# mainboard.net
KiCad netlist of a schematic drawn in Altium Designer
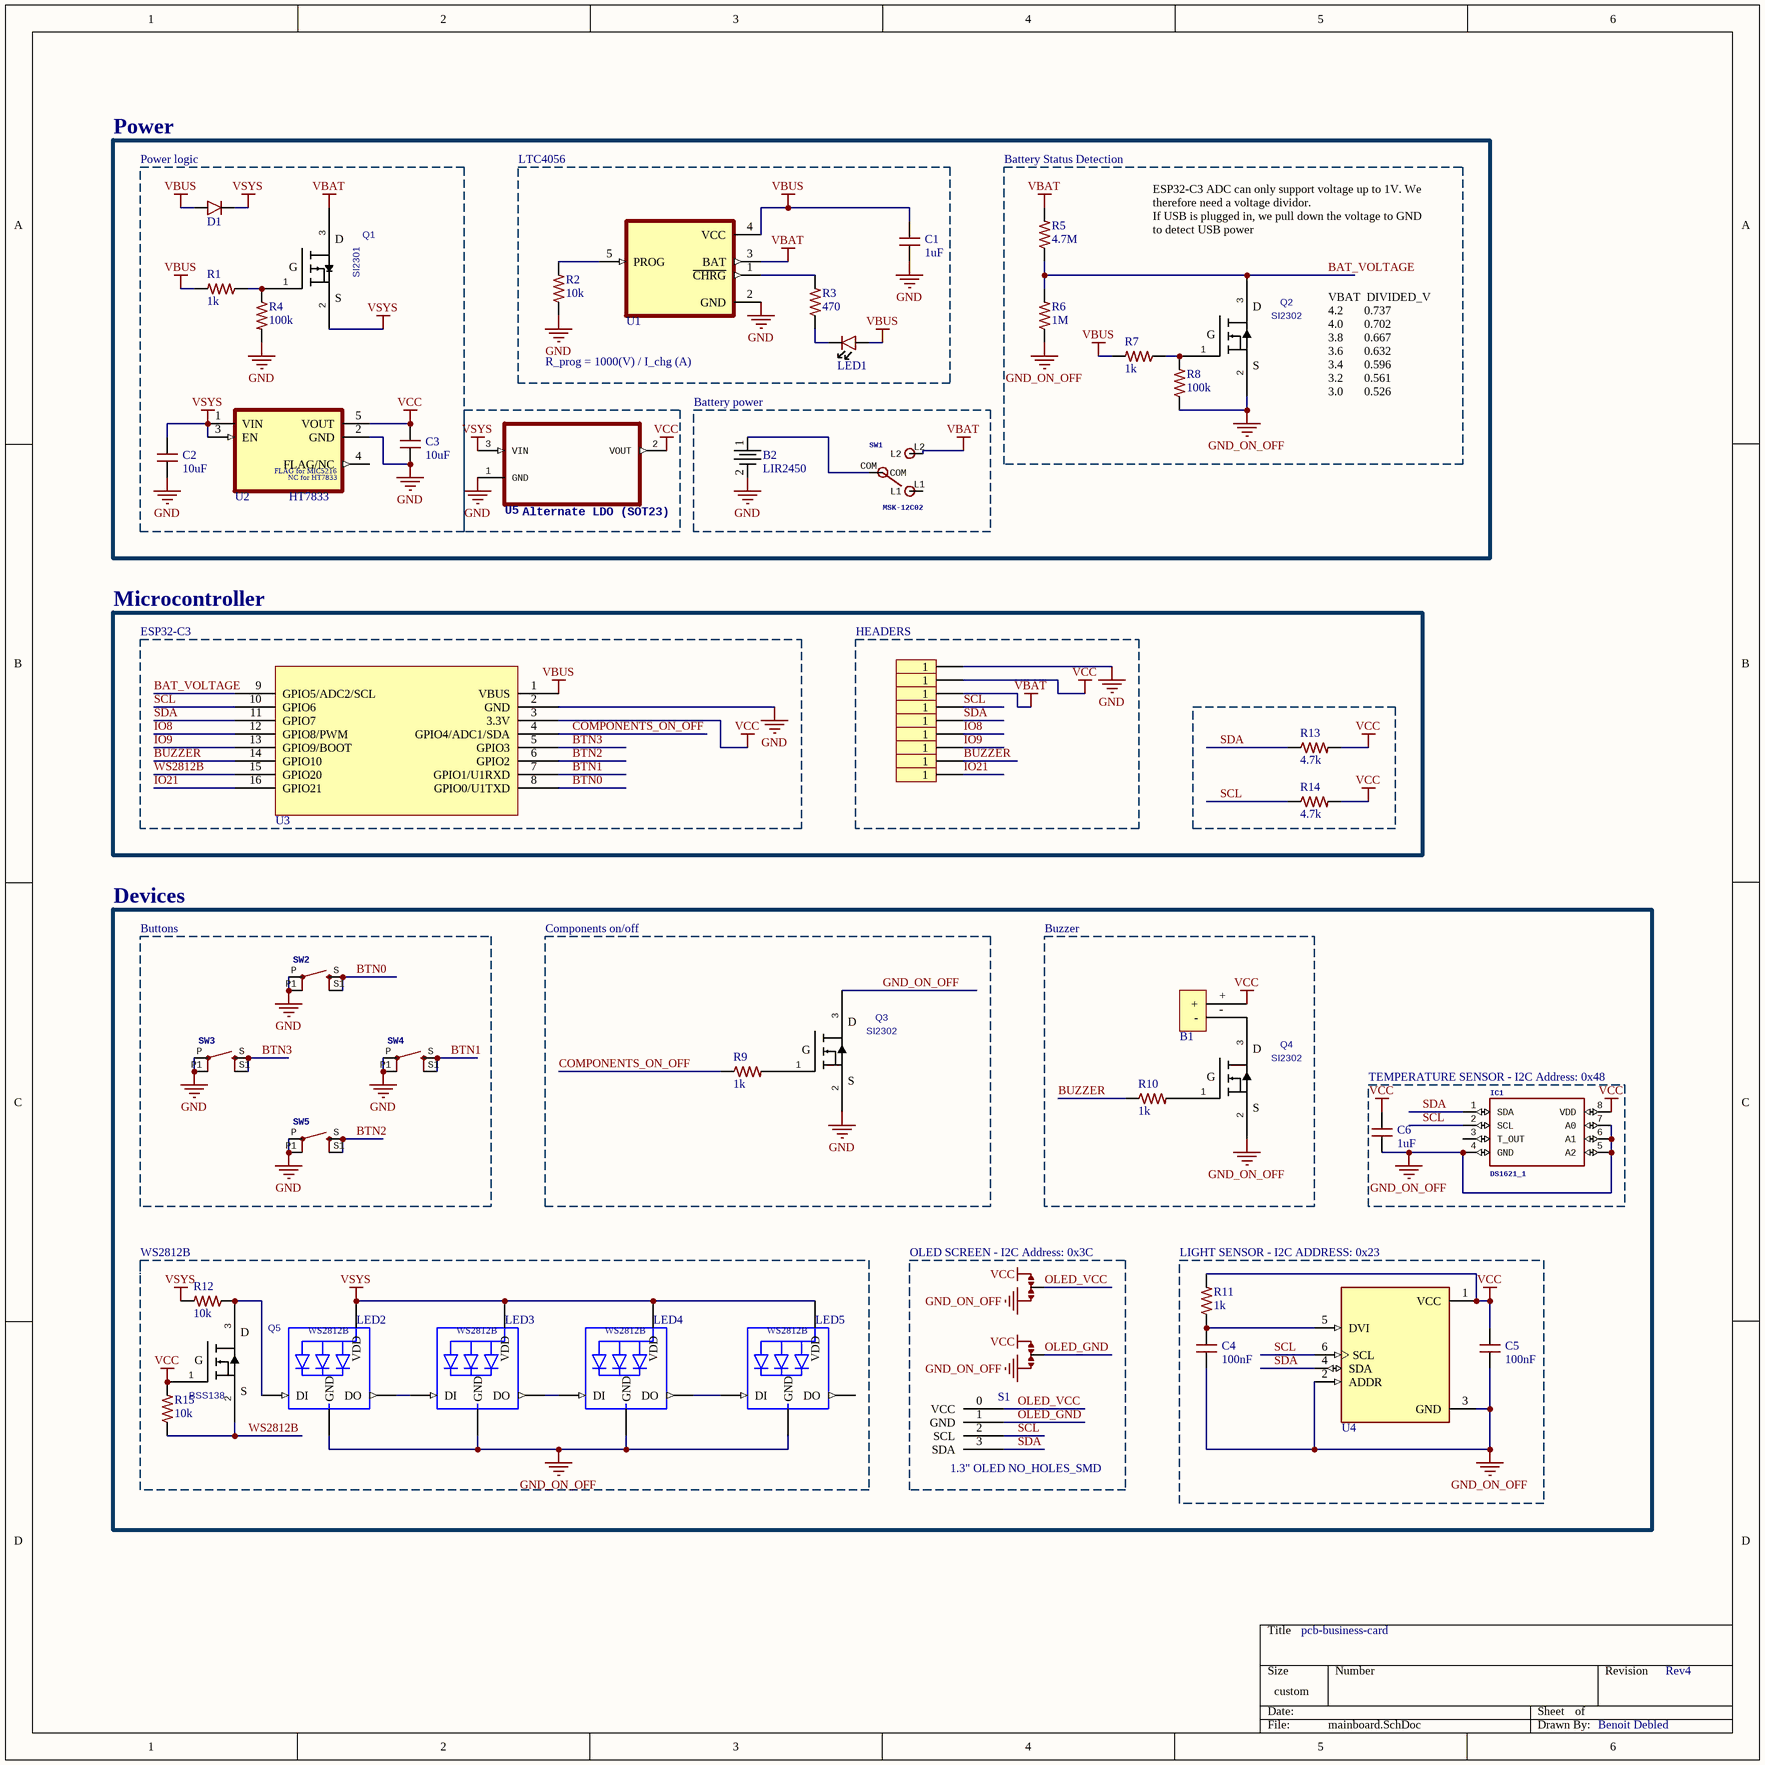
[diagram p0: mainboard.SchDoc]

(export (version "E")
  (design (tool "Eeschema 10.0.6"))
  (components
    (comp (ref "*")
      (value "PAD 1")
      (footprint "PAD_50mil_x_80mil")
      (libsource (lib "bd-header") (part "PAD 1"))
    )
    (comp (ref "*1")
      (value "PAD 1")
      (footprint "PAD_50mil_x_80mil")
      (libsource (lib "bd-header") (part "PAD 1"))
    )
    (comp (ref "*2")
      (value "PAD 1")
      (footprint "PAD_50mil_x_80mil")
      (libsource (lib "bd-header") (part "PAD 1"))
    )
    (comp (ref "*3")
      (value "PAD 1")
      (footprint "PAD_50mil_x_80mil")
      (libsource (lib "bd-header") (part "PAD 1"))
    )
    (comp (ref "*4")
      (value "PAD 1")
      (footprint "PAD_50mil_x_80mil")
      (libsource (lib "bd-header") (part "PAD 1"))
    )
    (comp (ref "*5")
      (value "PAD 1")
      (footprint "PAD_50mil_x_80mil")
      (libsource (lib "bd-header") (part "PAD 1"))
    )
    (comp (ref "*6")
      (value "PAD 1")
      (footprint "PAD_50mil_x_80mil")
      (libsource (lib "bd-header") (part "PAD 1"))
    )
    (comp (ref "*7")
      (value "PAD 1")
      (footprint "PAD_50mil_x_80mil")
      (libsource (lib "bd-header") (part "PAD 1"))
    )
    (comp (ref "*8")
      (value "PAD 1")
      (footprint "PAD_50mil_x_80mil")
      (libsource (lib "bd-header") (part "PAD 1"))
    )
    (comp (ref "B1")
      (value "Buzzer5x5x2")
      (footprint "BUZZER_5x5x2")
      (libsource (lib "bd-component") (part "Buzzer5x5x2"))
    )
    (comp (ref "B2")
      (value "LIR2450")
      (footprint "LIR2450")
      (libsource (lib "bd-component") (part "LIR2450"))
    )
    (comp (ref "C1") (value "1uF") (footprint "C0805K") (libsource (lib "bd-generics") (part "C-USC0805K")))
    (comp (ref "C2") (value "10uF") (footprint "C0805K") (libsource (lib "bd-generics") (part "C-USC0805K")))
    (comp (ref "C3") (value "10uF") (footprint "C0805K") (libsource (lib "bd-generics") (part "C-USC0805K")))
    (comp (ref "C4") (value "100nF") (footprint "C0805K") (libsource (lib "bd-generics") (part "C-USC0805K")))
    (comp (ref "C5") (value "100nF") (footprint "C0805K") (libsource (lib "bd-generics") (part "C-USC0805K")))
    (comp (ref "C6") (value "1uF") (footprint "C0805K") (libsource (lib "bd-generics") (part "C-USC0805K")))
    (comp (ref "D1")
      (value "Diode_M7")
      (footprint "DO-214")
      (libsource (lib "bd-generics") (part "Diode_M7"))
    )
    (comp (ref "IC1")
      (value "DS1621_1")
      (footprint "SOP-8")
      (libsource (lib "bd-component") (part "DS1621_1"))
    )
    (comp (ref "JMP1") (value "0R-JUMPA") (footprint "A0R-JMP") (libsource (lib "bd-misc") (part "0R-JUMPA")))
    (comp (ref "JMP2") (value "0R-JUMPA") (footprint "A0R-JMP") (libsource (lib "bd-misc") (part "0R-JUMPA")))
    (comp (ref "LED1") (value "LED") (footprint "LED0805K") (libsource (lib "bd-generics") (part "LED")))
    (comp (ref "LED2")
      (value "WS2812B")
      (footprint "WS2812B")
      (description "Raspberry Pi HAT _40 pin_ Wheeled Robotics Kit")
      (fields (field (name "MF") "SparkFun Electronics"))
      (libsource (lib "bd-component") (part "WS2812B"))
    )
    (comp (ref "LED3")
      (value "WS2812B")
      (footprint "WS2812B")
      (description "Raspberry Pi HAT _40 pin_ Wheeled Robotics Kit")
      (fields (field (name "MF") "SparkFun Electronics"))
      (libsource (lib "bd-component") (part "WS2812B"))
    )
    (comp (ref "LED4")
      (value "WS2812B")
      (footprint "WS2812B")
      (description "Raspberry Pi HAT _40 pin_ Wheeled Robotics Kit")
      (fields (field (name "MF") "SparkFun Electronics"))
      (libsource (lib "bd-component") (part "WS2812B"))
    )
    (comp (ref "LED5")
      (value "WS2812B")
      (footprint "WS2812B")
      (description "Raspberry Pi HAT _40 pin_ Wheeled Robotics Kit")
      (fields (field (name "MF") "SparkFun Electronics"))
      (libsource (lib "bd-component") (part "WS2812B"))
    )
    (comp (ref "Q1")
      (value "SI2301")
      (footprint "SOT-23")
      (fields
        (field (name "MANUFACTURER_PART_NUMBER") "IRLZ44NPBF")
        (field (name "COPYRIGHT") "Copyright (C) 2018 Accelerated Designs. All rights reserved")
      )
      (libsource (lib "bd-transistor") (part "SI2301"))
    )
    (comp (ref "Q2")
      (value "SI2302")
      (footprint "SOT-23")
      (fields
        (field (name "MANUFACTURER_PART_NUMBER") "IRLZ44NPBF")
        (field (name "COPYRIGHT") "Copyright (C) 2018 Accelerated Designs. All rights reserved")
      )
      (libsource (lib "bd-transistor") (part "SI2302"))
    )
    (comp (ref "Q3")
      (value "SI2302")
      (footprint "SOT-23")
      (fields
        (field (name "MANUFACTURER_PART_NUMBER") "IRLZ44NPBF")
        (field (name "COPYRIGHT") "Copyright (C) 2018 Accelerated Designs. All rights reserved")
      )
      (libsource (lib "bd-transistor") (part "SI2302"))
    )
    (comp (ref "Q4")
      (value "SI2302")
      (footprint "SOT-23")
      (fields
        (field (name "MANUFACTURER_PART_NUMBER") "IRLZ44NPBF")
        (field (name "COPYRIGHT") "Copyright (C) 2018 Accelerated Designs. All rights reserved")
      )
      (libsource (lib "bd-transistor") (part "SI2302"))
    )
    (comp (ref "Q5")
      (value "BSS138")
      (footprint "SOT-23")
      (fields
        (field (name "MANUFACTURER_PART_NUMBER") "IRLZ44NPBF")
        (field (name "COPYRIGHT") "Copyright (C) 2018 Accelerated Designs. All rights reserved")
      )
      (libsource (lib "bd-transistor") (part "SI2302"))
    )
    (comp (ref "R1") (value "1k") (footprint "R0805W") (libsource (lib "bd-generics") (part "R-US_R0805W")))
    (comp (ref "R2") (value "10k") (footprint "R0805W") (libsource (lib "bd-generics") (part "R-US_R0805W")))
    (comp (ref "R3") (value "470") (footprint "R0805W") (libsource (lib "bd-generics") (part "R-US_R0805W")))
    (comp (ref "R4") (value "100k") (footprint "R0805W") (libsource (lib "bd-generics") (part "R-US_R0805W")))
    (comp (ref "R5") (value "4.7M") (footprint "R0805W") (libsource (lib "bd-generics") (part "R-US_R0805W")))
    (comp (ref "R6") (value "1M") (footprint "R0805W") (libsource (lib "bd-generics") (part "R-US_R0805W")))
    (comp (ref "R7") (value "1k") (footprint "R0805W") (libsource (lib "bd-generics") (part "R-US_R0805W")))
    (comp (ref "R8") (value "100k") (footprint "R0805W") (libsource (lib "bd-generics") (part "R-US_R0805W")))
    (comp (ref "R9") (value "1k") (footprint "R0805W") (libsource (lib "bd-generics") (part "R-US_R0805W")))
    (comp (ref "R10") (value "1k") (footprint "R0805W") (libsource (lib "bd-generics") (part "R-US_R0805W")))
    (comp (ref "R11") (value "1k") (footprint "R0805W") (libsource (lib "bd-generics") (part "R-US_R0805W")))
    (comp (ref "R12") (value "10k") (footprint "R0805W") (libsource (lib "bd-generics") (part "R-US_R0805W")))
    (comp (ref "R13") (value "4.7k") (footprint "R0805K") (libsource (lib "bd-generics") (part "R-US_R0805")))
    (comp (ref "R14") (value "4.7k") (footprint "R0805K") (libsource (lib "bd-generics") (part "R-US_R0805")))
    (comp (ref "R15") (value "10k") (footprint "R0805W") (libsource (lib "bd-generics") (part "R-US_R0805W")))
    (comp (ref "S1")
      (value "1.3\" OLED NO_HOLES_SMD")
      (footprint "1.3_NO-holes_SMD")
      (libsource (lib "bd-display") (part "1.3{dblquote} OLED NO_HOLES_SMD"))
    )
    (comp (ref "SW1")
      (value "MSK-12C02")
      (footprint "MSK-12C02")
      (libsource (lib "bd-switch") (part "MSK-12C02"))
    )
    (comp (ref "SW2")
      (value "10-XX-6MD")
      (footprint "BT6X6")
      (libsource (lib "bd-switch") (part "10-XX-6MD"))
    )
    (comp (ref "SW3")
      (value "10-XX-6MD")
      (footprint "BT6X6")
      (libsource (lib "bd-switch") (part "10-XX-6MD"))
    )
    (comp (ref "SW4")
      (value "10-XX-6MD")
      (footprint "BT6X6")
      (libsource (lib "bd-switch") (part "10-XX-6MD"))
    )
    (comp (ref "SW5")
      (value "10-XX-6MD")
      (footprint "BT6X6")
      (libsource (lib "bd-switch") (part "10-XX-6MD"))
    )
    (comp (ref "U1")
      (value "LTC4054")
      (footprint "SOT23-5")
      (description "Battery Charger Li-Ion 10mA to 150mA 4.2V 5-Pin TSOT-23 T/R")
      (fields (field (name "MP") "LTC4054LES5-4.2#TRPBF") (field (name "MF") "Analog Devices"))
      (libsource (lib "bd-component") (part "LTC4054"))
    )
    (comp (ref "U2")
      (value "HT7833")
      (footprint "SOT23-5")
      (description "LDO Regulator")
      (fields (field (name "MP") "LTC4054LES5-4.2#TRPBF") (field (name "MF") "Analog Devices"))
      (libsource (lib "bd-component") (part "HT7833-MIC5216"))
    )
    (comp (ref "U3")
      (value "ESP32C3")
      (footprint "ESP32-C3-module")
      (libsource (lib "bd-microcontroller") (part "ESP32C3"))
    )
    (comp (ref "U4")
      (value "BH1750")
      (footprint "XDCR_BH1750FVI-TR")
      (description "Optical Sensor Ambient 560nm IÂ²C 6-SMD, Flat Lead Exposed Pad")
      (fields (field (name "MF") "Rohm") (field (name "MP") "BH1750FVI-TR"))
      (libsource (lib "bd-component") (part "BH1750"))
    )
    (comp (ref "U5")
      (value "Alternate LDO (SOT23)")
      (footprint "SOT95P237X112-3N")
      (fields (field (name "MPN") "MCP1700T-3302E/TT"))
      (libsource (lib "bd-component") (part "MCP1700T-3302E/TT"))
    )
  )
  (nets
    (net (code "1") (name "/BAT_VOLTAGE") (class "Default")
      (node (ref "Q2") (pin "3") (pinfunction "D_3") (pintype "passive"))
      (node (ref "R5") (pin "1") (pinfunction "1_1") (pintype "passive"))
      (node (ref "R6") (pin "2") (pinfunction "2_2") (pintype "passive"))
      (node (ref "U3") (pin "9") (pinfunction "GPIO5/ADC2/SCL_9") (pintype "passive"))
    )
    (net (code "2") (name "/BTN0") (class "Default")
      (node (ref "SW2") (pin "S") (pinfunction "S_S") (pintype "passive"))
      (node (ref "SW2") (pin "S1") (pinfunction "S1_S1") (pintype "passive"))
      (node (ref "U3") (pin "8") (pinfunction "GPIO0/U1TXD_8") (pintype "passive"))
    )
    (net (code "3") (name "/BTN1") (class "Default")
      (node (ref "SW4") (pin "S") (pinfunction "S_S") (pintype "passive"))
      (node (ref "SW4") (pin "S1") (pinfunction "S1_S1") (pintype "passive"))
      (node (ref "U3") (pin "7") (pinfunction "GPIO1/U1RXD_7") (pintype "passive"))
    )
    (net (code "4") (name "/BTN2") (class "Default")
      (node (ref "SW5") (pin "S") (pinfunction "S_S") (pintype "passive"))
      (node (ref "SW5") (pin "S1") (pinfunction "S1_S1") (pintype "passive"))
      (node (ref "U3") (pin "6") (pinfunction "GPIO2_6") (pintype "passive"))
    )
    (net (code "5") (name "/BTN3") (class "Default")
      (node (ref "SW3") (pin "S") (pinfunction "S_S") (pintype "passive"))
      (node (ref "SW3") (pin "S1") (pinfunction "S1_S1") (pintype "passive"))
      (node (ref "U3") (pin "5") (pinfunction "GPIO3_5") (pintype "passive"))
    )
    (net (code "6") (name "/BUZZER") (class "Default")
      (node (ref "*7") (pin "1") (pinfunction "1_1") (pintype "passive"))
      (node (ref "R10") (pin "1") (pinfunction "1_1") (pintype "passive"))
      (node (ref "U3") (pin "14") (pinfunction "GPIO10_14") (pintype "passive"))
    )
    (net (code "7") (name "/COMPONENTS_ON_OFF") (class "Default")
      (node (ref "R9") (pin "1") (pinfunction "1_1") (pintype "passive"))
      (node (ref "U3") (pin "4") (pinfunction "GPIO4/ADC1/SDA_4") (pintype "passive"))
    )
    (net (code "8") (name "/IO8") (class "Default")
      (node (ref "*5") (pin "1") (pinfunction "1_1") (pintype "passive"))
      (node (ref "U3") (pin "12") (pinfunction "GPIO8/PWM_12") (pintype "passive"))
    )
    (net (code "9") (name "/IO9") (class "Default")
      (node (ref "*6") (pin "1") (pinfunction "1_1") (pintype "passive"))
      (node (ref "U3") (pin "13") (pinfunction "GPIO9/BOOT_13") (pintype "passive"))
    )
    (net (code "10") (name "/IO21") (class "Default")
      (node (ref "*8") (pin "1") (pinfunction "1_1") (pintype "passive"))
      (node (ref "U3") (pin "16") (pinfunction "GPIO21_16") (pintype "passive"))
    )
    (net (code "11") (name "/OLED_GND") (class "Default")
      (node (ref "JMP2") (pin "2") (pinfunction "2_2") (pintype "passive"))
      (node (ref "S1") (pin "1") (pinfunction "GND_1") (pintype "passive"))
    )
    (net (code "12") (name "/OLED_VCC") (class "Default")
      (node (ref "JMP1") (pin "2") (pinfunction "2_2") (pintype "passive"))
      (node (ref "S1") (pin "0") (pinfunction "VCC_0") (pintype "passive"))
    )
    (net (code "13") (name "/SCL") (class "Default")
      (node (ref "*3") (pin "1") (pinfunction "1_1") (pintype "passive"))
      (node (ref "IC1") (pin "2") (pinfunction "SCL_2") (pintype "bidirectional"))
      (node (ref "R14") (pin "1") (pinfunction "1_1") (pintype "passive"))
      (node (ref "S1") (pin "2") (pinfunction "SCL_2") (pintype "passive"))
      (node (ref "U3") (pin "10") (pinfunction "GPIO6_10") (pintype "passive"))
      (node (ref "U4") (pin "6") (pinfunction "SCL_6") (pintype "input"))
    )
    (net (code "14") (name "/SDA") (class "Default")
      (node (ref "*4") (pin "1") (pinfunction "1_1") (pintype "passive"))
      (node (ref "IC1") (pin "1") (pinfunction "SDA_1") (pintype "bidirectional"))
      (node (ref "R13") (pin "1") (pinfunction "1_1") (pintype "passive"))
      (node (ref "S1") (pin "3") (pinfunction "SDA_3") (pintype "passive"))
      (node (ref "U3") (pin "11") (pinfunction "GPIO7_11") (pintype "passive"))
      (node (ref "U4") (pin "4") (pinfunction "SDA_4") (pintype "bidirectional"))
    )
    (net (code "15") (name "/WS2812B") (class "Default")
      (node (ref "Q5") (pin "2") (pinfunction "S_2") (pintype "passive"))
      (node (ref "R15") (pin "1") (pinfunction "1_1") (pintype "passive"))
      (node (ref "U3") (pin "15") (pinfunction "GPIO20_15") (pintype "passive"))
    )
    (net (code "16") (name "GND") (class "Default")
      (node (ref "*") (pin "1") (pinfunction "1_1") (pintype "passive"))
      (node (ref "B2") (pin "2") (pinfunction "-_2") (pintype "passive"))
      (node (ref "C1") (pin "2") (pinfunction "2_2") (pintype "passive"))
      (node (ref "C2") (pin "2") (pinfunction "2_2") (pintype "passive"))
      (node (ref "C3") (pin "2") (pinfunction "2_2") (pintype "passive"))
      (node (ref "Q3") (pin "2") (pinfunction "S_2") (pintype "passive"))
      (node (ref "R2") (pin "1") (pinfunction "1_1") (pintype "passive"))
      (node (ref "R4") (pin "2") (pinfunction "2_2") (pintype "passive"))
      (node (ref "SW2") (pin "P") (pinfunction "P_P") (pintype "passive"))
      (node (ref "SW2") (pin "P1") (pinfunction "P1_P1") (pintype "passive"))
      (node (ref "SW3") (pin "P") (pinfunction "P_P") (pintype "passive"))
      (node (ref "SW3") (pin "P1") (pinfunction "P1_P1") (pintype "passive"))
      (node (ref "SW4") (pin "P") (pinfunction "P_P") (pintype "passive"))
      (node (ref "SW4") (pin "P1") (pinfunction "P1_P1") (pintype "passive"))
      (node (ref "SW5") (pin "P") (pinfunction "P_P") (pintype "passive"))
      (node (ref "SW5") (pin "P1") (pinfunction "P1_P1") (pintype "passive"))
      (node (ref "U1") (pin "2") (pinfunction "GND_2") (pintype "power_in"))
      (node (ref "U2") (pin "2") (pinfunction "GND_2") (pintype "power_in"))
      (node (ref "U3") (pin "2") (pinfunction "GND_2") (pintype "passive"))
      (node (ref "U5") (pin "1") (pinfunction "GND_1") (pintype "passive"))
    )
    (net (code "17") (name "GND_ON_OFF") (class "Default")
      (node (ref "C4") (pin "2") (pinfunction "2_2") (pintype "passive"))
      (node (ref "C5") (pin "2") (pinfunction "2_2") (pintype "passive"))
      (node (ref "C6") (pin "2") (pinfunction "2_2") (pintype "passive"))
      (node (ref "IC1") (pin "4") (pinfunction "GND_4") (pintype "bidirectional"))
      (node (ref "IC1") (pin "5") (pinfunction "A2_5") (pintype "bidirectional"))
      (node (ref "IC1") (pin "6") (pinfunction "A1_6") (pintype "bidirectional"))
      (node (ref "IC1") (pin "7") (pinfunction "A0_7") (pintype "bidirectional"))
      (node (ref "JMP1") (pin "3") (pinfunction "3_3") (pintype "passive"))
      (node (ref "JMP2") (pin "3") (pinfunction "3_3") (pintype "passive"))
      (node (ref "LED2") (pin "3-GND") (pinfunction "GND_3-GND") (pintype "power_in"))
      (node (ref "LED3") (pin "3-GND") (pinfunction "GND_3-GND") (pintype "power_in"))
      (node (ref "LED4") (pin "3-GND") (pinfunction "GND_3-GND") (pintype "power_in"))
      (node (ref "LED5") (pin "3-GND") (pinfunction "GND_3-GND") (pintype "power_in"))
      (node (ref "Q2") (pin "2") (pinfunction "S_2") (pintype "passive"))
      (node (ref "Q3") (pin "3") (pinfunction "D_3") (pintype "passive"))
      (node (ref "Q4") (pin "2") (pinfunction "S_2") (pintype "passive"))
      (node (ref "R6") (pin "1") (pinfunction "1_1") (pintype "passive"))
      (node (ref "R8") (pin "1") (pinfunction "1_1") (pintype "passive"))
      (node (ref "U4") (pin "2") (pinfunction "ADDR_2") (pintype "input"))
      (node (ref "U4") (pin "3") (pinfunction "GND_3") (pintype "power_in"))
    )
    (net (code "18") (name "Net-(B2-+)") (class "Default")
      (node (ref "B2") (pin "1") (pinfunction "+_1") (pintype "passive"))
      (node (ref "SW1") (pin "COM") (pinfunction "COM_COM") (pintype "bidirectional"))
    )
    (net (code "19") (name "Net-(LED1-Pad2)") (class "Default")
      (node (ref "LED1") (pin "2") (pinfunction "2_2") (pintype "passive"))
      (node (ref "R3") (pin "1") (pinfunction "1_1") (pintype "passive"))
    )
    (net (code "20") (name "Net-(LED2-DI)") (class "Default")
      (node (ref "LED2") (pin "4-DIN") (pinfunction "DI_4-DIN") (pintype "input"))
      (node (ref "Q5") (pin "3") (pinfunction "D_3") (pintype "passive"))
      (node (ref "R12") (pin "1") (pinfunction "1_1") (pintype "passive"))
    )
    (net (code "21") (name "Net-(LED2-DO)") (class "Default")
      (node (ref "LED2") (pin "2-DOUT") (pinfunction "DO_2-DOUT") (pintype "output"))
      (node (ref "LED3") (pin "4-DIN") (pinfunction "DI_4-DIN") (pintype "input"))
    )
    (net (code "22") (name "Net-(LED3-DO)") (class "Default")
      (node (ref "LED3") (pin "2-DOUT") (pinfunction "DO_2-DOUT") (pintype "output"))
      (node (ref "LED4") (pin "4-DIN") (pinfunction "DI_4-DIN") (pintype "input"))
    )
    (net (code "23") (name "Net-(LED4-DO)") (class "Default")
      (node (ref "LED4") (pin "2-DOUT") (pinfunction "DO_2-DOUT") (pintype "output"))
      (node (ref "LED5") (pin "4-DIN") (pinfunction "DI_4-DIN") (pintype "input"))
    )
    (net (code "24") (name "Net-(Q1-G)") (class "Default")
      (node (ref "Q1") (pin "1") (pinfunction "G_1") (pintype "passive"))
      (node (ref "R1") (pin "1") (pinfunction "1_1") (pintype "passive"))
      (node (ref "R4") (pin "1") (pinfunction "1_1") (pintype "passive"))
    )
    (net (code "25") (name "Net-(Q2-G)") (class "Default")
      (node (ref "Q2") (pin "1") (pinfunction "G_1") (pintype "passive"))
      (node (ref "R7") (pin "1") (pinfunction "1_1") (pintype "passive"))
      (node (ref "R8") (pin "2") (pinfunction "2_2") (pintype "passive"))
    )
    (net (code "26") (name "Net-(Q3-G)") (class "Default")
      (node (ref "Q3") (pin "1") (pinfunction "G_1") (pintype "passive"))
      (node (ref "R9") (pin "2") (pinfunction "2_2") (pintype "passive"))
    )
    (net (code "27") (name "Net-(Q4-D)") (class "Default")
      (node (ref "B1") (pin "-") (pinfunction "-_-") (pintype "passive"))
      (node (ref "Q4") (pin "3") (pinfunction "D_3") (pintype "passive"))
    )
    (net (code "28") (name "Net-(Q4-G)") (class "Default")
      (node (ref "Q4") (pin "1") (pinfunction "G_1") (pintype "passive"))
      (node (ref "R10") (pin "2") (pinfunction "2_2") (pintype "passive"))
    )
    (net (code "29") (name "Net-(U1-PROG)") (class "Default")
      (node (ref "R2") (pin "2") (pinfunction "2_2") (pintype "passive"))
      (node (ref "U1") (pin "5") (pinfunction "PROG_5") (pintype "input"))
    )
    (net (code "30") (name "Net-(U1-~{CHRG})") (class "Default")
      (node (ref "R3") (pin "2") (pinfunction "2_2") (pintype "passive"))
      (node (ref "U1") (pin "1") (pinfunction "~{CHRG}_1") (pintype "output"))
    )
    (net (code "31") (name "Net-(U4-DVI)") (class "Default")
      (node (ref "C4") (pin "1") (pinfunction "1_1") (pintype "passive"))
      (node (ref "R11") (pin "1") (pinfunction "1_1") (pintype "passive"))
      (node (ref "U4") (pin "5") (pinfunction "DVI_5") (pintype "input"))
    )
    (net (code "32") (name "VBAT") (class "Default")
      (node (ref "*2") (pin "1") (pinfunction "1_1") (pintype "passive"))
      (node (ref "Q1") (pin "3") (pinfunction "D_3") (pintype "passive"))
      (node (ref "R5") (pin "2") (pinfunction "2_2") (pintype "passive"))
      (node (ref "SW1") (pin "L2") (pinfunction "L2_L2") (pintype "bidirectional"))
      (node (ref "U1") (pin "3") (pinfunction "BAT_3") (pintype "output"))
    )
    (net (code "33") (name "VBUS") (class "Default")
      (node (ref "C1") (pin "1") (pinfunction "1_1") (pintype "passive"))
      (node (ref "D1") (pin "A") (pinfunction "1_A") (pintype "passive"))
      (node (ref "LED1") (pin "1") (pinfunction "1_1") (pintype "passive"))
      (node (ref "R1") (pin "2") (pinfunction "2_2") (pintype "passive"))
      (node (ref "R7") (pin "2") (pinfunction "2_2") (pintype "passive"))
      (node (ref "U1") (pin "4") (pinfunction "VCC_4") (pintype "power_in"))
      (node (ref "U3") (pin "1") (pinfunction "VBUS_1") (pintype "passive"))
    )
    (net (code "34") (name "VCC") (class "Default")
      (node (ref "*1") (pin "1") (pinfunction "1_1") (pintype "passive"))
      (node (ref "B1") (pin "+") (pinfunction "+_+") (pintype "passive"))
      (node (ref "C3") (pin "1") (pinfunction "1_1") (pintype "passive"))
      (node (ref "C5") (pin "1") (pinfunction "1_1") (pintype "passive"))
      (node (ref "C6") (pin "1") (pinfunction "1_1") (pintype "passive"))
      (node (ref "IC1") (pin "8") (pinfunction "VDD_8") (pintype "bidirectional"))
      (node (ref "JMP1") (pin "1") (pinfunction "1_1") (pintype "passive"))
      (node (ref "JMP2") (pin "1") (pinfunction "1_1") (pintype "passive"))
      (node (ref "Q5") (pin "1") (pinfunction "G_1") (pintype "passive"))
      (node (ref "R11") (pin "2") (pinfunction "2_2") (pintype "passive"))
      (node (ref "R13") (pin "2") (pinfunction "2_2") (pintype "passive"))
      (node (ref "R14") (pin "2") (pinfunction "2_2") (pintype "passive"))
      (node (ref "R15") (pin "2") (pinfunction "2_2") (pintype "passive"))
      (node (ref "U2") (pin "5") (pinfunction "VOUT_5") (pintype "power_in"))
      (node (ref "U3") (pin "3") (pinfunction "3.3V_3") (pintype "passive"))
      (node (ref "U4") (pin "1") (pinfunction "VCC_1") (pintype "power_in"))
      (node (ref "U5") (pin "2") (pinfunction "VOUT_2") (pintype "output"))
    )
    (net (code "35") (name "VSYS") (class "Default")
      (node (ref "C2") (pin "1") (pinfunction "1_1") (pintype "passive"))
      (node (ref "D1") (pin "C") (pinfunction "2_C") (pintype "passive"))
      (node (ref "LED2") (pin "1-VDD") (pinfunction "VDD_1-VDD") (pintype "power_in"))
      (node (ref "LED3") (pin "1-VDD") (pinfunction "VDD_1-VDD") (pintype "power_in"))
      (node (ref "LED4") (pin "1-VDD") (pinfunction "VDD_1-VDD") (pintype "power_in"))
      (node (ref "LED5") (pin "1-VDD") (pinfunction "VDD_1-VDD") (pintype "power_in"))
      (node (ref "Q1") (pin "2") (pinfunction "S_2") (pintype "passive"))
      (node (ref "R12") (pin "2") (pinfunction "2_2") (pintype "passive"))
      (node (ref "U2") (pin "1") (pinfunction "VIN_1") (pintype "power_in"))
      (node (ref "U2") (pin "3") (pinfunction "EN_3") (pintype "input"))
      (node (ref "U5") (pin "3") (pinfunction "VIN_3") (pintype "input"))
    )
    (net (code "36") (name "unconnected-(IC1-T_OUT-Pad3)") (class "Default")
      (node (ref "IC1") (pin "3") (pinfunction "T_OUT_3") (pintype "bidirectional"))
    )
    (net (code "37") (name "unconnected-(LED5-DO-Pad2-DOUT)") (class "Default")
      (node (ref "LED5") (pin "2-DOUT") (pinfunction "DO_2-DOUT") (pintype "output"))
    )
    (net (code "38") (name "unconnected-(SW1-PadL1)") (class "Default")
      (node (ref "SW1") (pin "L1") (pinfunction "L1_L1") (pintype "bidirectional"))
    )
    (net (code "39") (name "unconnected-(U2-FLAG{slash}NC-Pad4)") (class "Default")
      (node (ref "U2") (pin "4") (pinfunction "FLAG/NC_4") (pintype "output"))
    )
  )
)
